# PCB_Maze.net
KiCad netlist of a schematic drawn in EAGLE
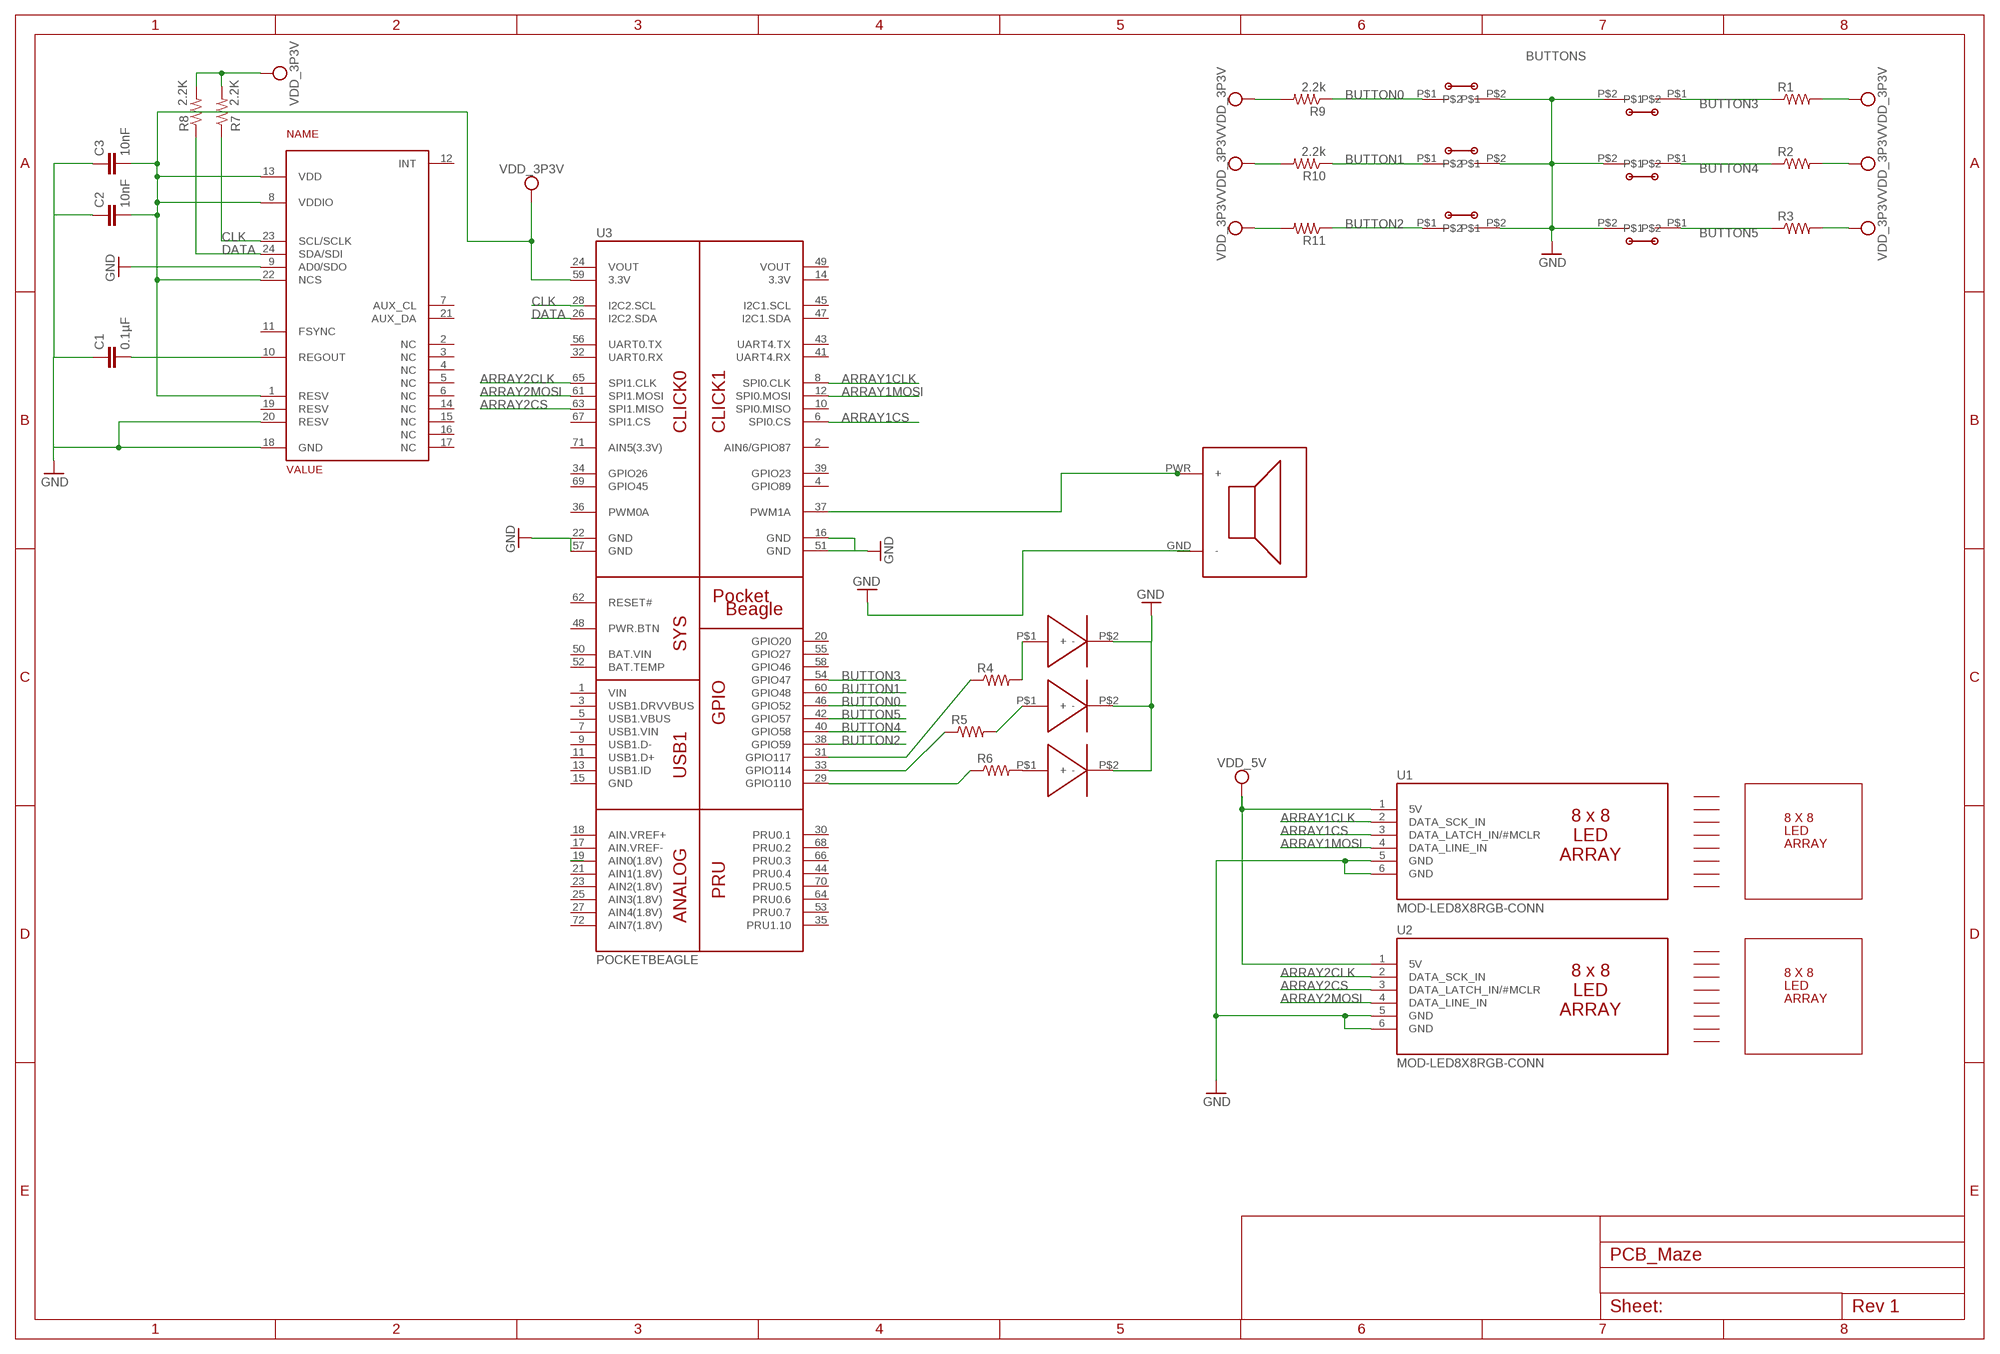
[diagram p0: schematic, sheet 1]

(export (version "E")
  (design (tool "Eeschema 10.0.6"))
  (components
    (comp (ref "C1")
      (value "0.1µF")
      (footprint "eagle-import:C0402")
      (libsource (lib "eagle-import") (part "C_C0402"))
    )
    (comp (ref "C2")
      (value "10nF")
      (footprint "eagle-import:C0402")
      (libsource (lib "eagle-import") (part "C_C0402"))
    )
    (comp (ref "C3")
      (value "10nF")
      (footprint "eagle-import:C0402")
      (libsource (lib "eagle-import") (part "C_C0402"))
    )
    (comp (ref "R1")
      (value "R_R0402")
      (footprint "eagle-import:R0402")
      (libsource (lib "eagle-import") (part "R_R0402"))
    )
    (comp (ref "R2")
      (value "R_R0402")
      (footprint "eagle-import:R0402")
      (libsource (lib "eagle-import") (part "R_R0402"))
    )
    (comp (ref "R3")
      (value "R_R0402")
      (footprint "eagle-import:R0402")
      (libsource (lib "eagle-import") (part "R_R0402"))
    )
    (comp (ref "R4")
      (value "R_R0402")
      (footprint "eagle-import:R0402")
      (libsource (lib "eagle-import") (part "R_R0402"))
    )
    (comp (ref "R5")
      (value "R_R0402")
      (footprint "eagle-import:R0402")
      (libsource (lib "eagle-import") (part "R_R0402"))
    )
    (comp (ref "R6")
      (value "R_R0402")
      (footprint "eagle-import:R0402")
      (libsource (lib "eagle-import") (part "R_R0402"))
    )
    (comp (ref "R7")
      (value "2.2K")
      (footprint "eagle-import:R0402")
      (libsource (lib "eagle-import") (part "R_R0402"))
    )
    (comp (ref "R8")
      (value "2.2K")
      (footprint "eagle-import:R0402")
      (libsource (lib "eagle-import") (part "R_R0402"))
    )
    (comp (ref "R9")
      (value "2.2k")
      (footprint "eagle-import:R0402")
      (libsource (lib "eagle-import") (part "R_R0402"))
    )
    (comp (ref "R10")
      (value "2.2k")
      (footprint "eagle-import:R0402")
      (libsource (lib "eagle-import") (part "R_R0402"))
    )
    (comp (ref "R11")
      (value "R_R0402")
      (footprint "eagle-import:R0402")
      (libsource (lib "eagle-import") (part "R_R0402"))
    )
    (comp (ref "U$1")
      (value "BUTTON")
      (footprint "eagle-import:SC203")
      (libsource (lib "eagle-import") (part "BUTTON"))
    )
    (comp (ref "U$2")
      (value "BUTTON")
      (footprint "eagle-import:SC203")
      (libsource (lib "eagle-import") (part "BUTTON"))
    )
    (comp (ref "U$3")
      (value "BUTTON")
      (footprint "eagle-import:SC203")
      (libsource (lib "eagle-import") (part "BUTTON"))
    )
    (comp (ref "U$5")
      (value "BUTTON")
      (footprint "eagle-import:SC203")
      (libsource (lib "eagle-import") (part "BUTTON"))
    )
    (comp (ref "U$6")
      (value "BUTTON")
      (footprint "eagle-import:SC203")
      (libsource (lib "eagle-import") (part "BUTTON"))
    )
    (comp (ref "U$8")
      (value "LED")
      (footprint "eagle-import:C191TBKT")
      (libsource (lib "eagle-import") (part "LED"))
    )
    (comp (ref "U$9")
      (value "LED")
      (footprint "eagle-import:C191TBKT")
      (libsource (lib "eagle-import") (part "LED"))
    )
    (comp (ref "U$10")
      (value "LED")
      (footprint "eagle-import:C191TBKT")
      (libsource (lib "eagle-import") (part "LED"))
    )
    (comp (ref "U$11")
      (value "BUZZER")
      (footprint "eagle-import:CEM-1203")
      (libsource (lib "eagle-import") (part "BUZZER"))
    )
    (comp (ref "U$12")
      (value "MPU9250")
      (footprint "eagle-import:QFN_3MMX3MM")
      (libsource (lib "eagle-import") (part "MPU9250"))
    )
    (comp (ref "U$13")
      (value "BUTTON")
      (footprint "eagle-import:SC203")
      (libsource (lib "eagle-import") (part "BUTTON"))
    )
    (comp (ref "U1")
      (value "MOD-LED8X8RGB-CONN")
      (footprint "eagle-import:FE06W")
      (libsource (lib "eagle-import") (part "MOD-LED8X8RGB-CONN"))
    )
    (comp (ref "U2")
      (value "MOD-LED8X8RGB-CONN")
      (footprint "eagle-import:FE06W")
      (libsource (lib "eagle-import") (part "MOD-LED8X8RGB-CONN"))
    )
    (comp (ref "U3")
      (value "POCKETBEAGLE")
      (footprint "eagle-import:POCKETBEAGLE")
      (libsource (lib "eagle-import") (part "POCKETBEAGLE"))
    )
  )
  (nets
    (net (code "1") (name "/ARRAY1CLK") (class "Default")
      (node (ref "U1") (pin "2") (pinfunction "DATA_SCK_IN_2") (pintype "bidirectional"))
      (node (ref "U3") (pin "8") (pinfunction "SPI0.CLK_8") (pintype "bidirectional"))
    )
    (net (code "2") (name "/ARRAY1CS") (class "Default")
      (node (ref "U1") (pin "3") (pinfunction "DATA_LATCH_IN/#MCLR_3") (pintype "bidirectional"))
      (node (ref "U3") (pin "6") (pinfunction "SPI0.CS_6") (pintype "bidirectional"))
    )
    (net (code "3") (name "/ARRAY1MOSI") (class "Default")
      (node (ref "U1") (pin "4") (pinfunction "DATA_LINE_IN_4") (pintype "bidirectional"))
      (node (ref "U3") (pin "12") (pinfunction "SPI0.MOSI_12") (pintype "bidirectional"))
    )
    (net (code "4") (name "/ARRAY2CLK") (class "Default")
      (node (ref "U2") (pin "2") (pinfunction "DATA_SCK_IN_2") (pintype "bidirectional"))
      (node (ref "U3") (pin "65") (pinfunction "SPI1.CLK_65") (pintype "bidirectional"))
    )
    (net (code "5") (name "/ARRAY2CS") (class "Default")
      (node (ref "U2") (pin "3") (pinfunction "DATA_LATCH_IN/#MCLR_3") (pintype "bidirectional"))
      (node (ref "U3") (pin "63") (pinfunction "SPI1.MISO_63") (pintype "bidirectional"))
    )
    (net (code "6") (name "/ARRAY2MOSI") (class "Default")
      (node (ref "U2") (pin "4") (pinfunction "DATA_LINE_IN_4") (pintype "bidirectional"))
      (node (ref "U3") (pin "61") (pinfunction "SPI1.MOSI_61") (pintype "bidirectional"))
    )
    (net (code "7") (name "/BUTTON0") (class "Default")
      (node (ref "R9") (pin "1") (pinfunction "1_1") (pintype "passive"))
      (node (ref "U$5") (pin "P$1") (pinfunction "P$1_P$1") (pintype "bidirectional"))
      (node (ref "U3") (pin "46") (pinfunction "GPIO52_46") (pintype "bidirectional"))
    )
    (net (code "8") (name "/BUTTON1") (class "Default")
      (node (ref "R10") (pin "1") (pinfunction "1_1") (pintype "passive"))
      (node (ref "U$6") (pin "P$1") (pinfunction "P$1_P$1") (pintype "bidirectional"))
      (node (ref "U3") (pin "60") (pinfunction "GPIO48_60") (pintype "bidirectional"))
    )
    (net (code "9") (name "/BUTTON2") (class "Default")
      (node (ref "R11") (pin "1") (pinfunction "1_1") (pintype "passive"))
      (node (ref "U$13") (pin "P$1") (pinfunction "P$1_P$1") (pintype "bidirectional"))
      (node (ref "U3") (pin "38") (pinfunction "GPIO59_38") (pintype "bidirectional"))
    )
    (net (code "10") (name "/BUTTON3") (class "Default")
      (node (ref "R1") (pin "1") (pinfunction "1_1") (pintype "passive"))
      (node (ref "U$1") (pin "P$1") (pinfunction "P$1_P$1") (pintype "bidirectional"))
      (node (ref "U3") (pin "54") (pinfunction "GPIO47_54") (pintype "bidirectional"))
    )
    (net (code "11") (name "/BUTTON4") (class "Default")
      (node (ref "R2") (pin "1") (pinfunction "1_1") (pintype "passive"))
      (node (ref "U$2") (pin "P$1") (pinfunction "P$1_P$1") (pintype "bidirectional"))
      (node (ref "U3") (pin "40") (pinfunction "GPIO58_40") (pintype "bidirectional"))
    )
    (net (code "12") (name "/BUTTON5") (class "Default")
      (node (ref "R3") (pin "1") (pinfunction "1_1") (pintype "passive"))
      (node (ref "U$3") (pin "P$1") (pinfunction "P$1_P$1") (pintype "bidirectional"))
      (node (ref "U3") (pin "42") (pinfunction "GPIO57_42") (pintype "bidirectional"))
    )
    (net (code "13") (name "/CLK") (class "Default")
      (node (ref "R7") (pin "1") (pinfunction "1_1") (pintype "passive"))
      (node (ref "U$12") (pin "23") (pinfunction "SCL/SCLK_23") (pintype "bidirectional"))
      (node (ref "U3") (pin "28") (pinfunction "I2C2.SCL_28") (pintype "bidirectional"))
    )
    (net (code "14") (name "/DATA") (class "Default")
      (node (ref "R8") (pin "1") (pinfunction "1_1") (pintype "passive"))
      (node (ref "U$12") (pin "24") (pinfunction "SDA/SDI_24") (pintype "bidirectional"))
      (node (ref "U3") (pin "26") (pinfunction "I2C2.SDA_26") (pintype "bidirectional"))
    )
    (net (code "15") (name "GND") (class "Default")
      (node (ref "C1") (pin "1") (pinfunction "1_1") (pintype "passive"))
      (node (ref "C2") (pin "1") (pinfunction "1_1") (pintype "passive"))
      (node (ref "C3") (pin "1") (pinfunction "1_1") (pintype "passive"))
      (node (ref "U$1") (pin "P$2") (pinfunction "P$2_P$2") (pintype "bidirectional"))
      (node (ref "U$10") (pin "P$2") (pinfunction "-_P$2") (pintype "bidirectional"))
      (node (ref "U$12") (pin "18") (pinfunction "GND_18") (pintype "bidirectional"))
      (node (ref "U$12") (pin "20") (pinfunction "RESV_20") (pintype "bidirectional"))
      (node (ref "U$12") (pin "9") (pinfunction "AD0/SDO_9") (pintype "bidirectional"))
      (node (ref "U$13") (pin "P$2") (pinfunction "P$2_P$2") (pintype "bidirectional"))
      (node (ref "U$2") (pin "P$2") (pinfunction "P$2_P$2") (pintype "bidirectional"))
      (node (ref "U$3") (pin "P$2") (pinfunction "P$2_P$2") (pintype "bidirectional"))
      (node (ref "U$5") (pin "P$2") (pinfunction "P$2_P$2") (pintype "bidirectional"))
      (node (ref "U$6") (pin "P$2") (pinfunction "P$2_P$2") (pintype "bidirectional"))
      (node (ref "U$8") (pin "P$2") (pinfunction "-_P$2") (pintype "bidirectional"))
      (node (ref "U$9") (pin "P$2") (pinfunction "-_P$2") (pintype "bidirectional"))
      (node (ref "U1") (pin "5") (pinfunction "GND_5") (pintype "bidirectional"))
      (node (ref "U1") (pin "6") (pinfunction "GND_6") (pintype "bidirectional"))
      (node (ref "U2") (pin "5") (pinfunction "GND_5") (pintype "bidirectional"))
      (node (ref "U2") (pin "6") (pinfunction "GND_6") (pintype "bidirectional"))
      (node (ref "U3") (pin "16") (pinfunction "GND_16") (pintype "bidirectional"))
      (node (ref "U3") (pin "22") (pinfunction "GND_22") (pintype "bidirectional"))
      (node (ref "U3") (pin "51") (pinfunction "GND_51") (pintype "bidirectional"))
      (node (ref "U3") (pin "57") (pinfunction "GND_57") (pintype "bidirectional"))
    )
    (net (code "16") (name "Net-(U$8-+)") (class "Default")
      (node (ref "R4") (pin "2") (pinfunction "2_2") (pintype "passive"))
      (node (ref "U$8") (pin "P$1") (pinfunction "+_P$1") (pintype "bidirectional"))
    )
    (net (code "17") (name "Net-(U$9-+)") (class "Default")
      (node (ref "R5") (pin "2") (pinfunction "2_2") (pintype "passive"))
      (node (ref "U$9") (pin "P$1") (pinfunction "+_P$1") (pintype "bidirectional"))
    )
    (net (code "18") (name "Net-(U$10-+)") (class "Default")
      (node (ref "R6") (pin "2") (pinfunction "2_2") (pintype "passive"))
      (node (ref "U$10") (pin "P$1") (pinfunction "+_P$1") (pintype "bidirectional"))
    )
    (net (code "19") (name "Net-(U$11-+)") (class "Default")
      (node (ref "U$11") (pin "PWR") (pinfunction "+_PWR") (pintype "bidirectional"))
      (node (ref "U3") (pin "37") (pinfunction "PWM1A_37") (pintype "bidirectional"))
    )
    (net (code "20") (name "Net-(U$12-REGOUT)") (class "Default")
      (node (ref "C1") (pin "2") (pinfunction "2_2") (pintype "passive"))
      (node (ref "U$12") (pin "10") (pinfunction "REGOUT_10") (pintype "bidirectional"))
    )
    (net (code "21") (name "Net-(U3-GPIO110)") (class "Default")
      (node (ref "R6") (pin "1") (pinfunction "1_1") (pintype "passive"))
      (node (ref "U3") (pin "29") (pinfunction "GPIO110_29") (pintype "bidirectional"))
    )
    (net (code "22") (name "Net-(U3-GPIO114)") (class "Default")
      (node (ref "R5") (pin "1") (pinfunction "1_1") (pintype "passive"))
      (node (ref "U3") (pin "33") (pinfunction "GPIO114_33") (pintype "bidirectional"))
    )
    (net (code "23") (name "Net-(U3-GPIO117)") (class "Default")
      (node (ref "R4") (pin "1") (pinfunction "1_1") (pintype "passive"))
      (node (ref "U3") (pin "31") (pinfunction "GPIO117_31") (pintype "bidirectional"))
    )
    (net (code "24") (name "VDD_3P3V") (class "Default")
      (node (ref "C2") (pin "2") (pinfunction "2_2") (pintype "passive"))
      (node (ref "C3") (pin "2") (pinfunction "2_2") (pintype "passive"))
      (node (ref "R1") (pin "2") (pinfunction "2_2") (pintype "passive"))
      (node (ref "R10") (pin "2") (pinfunction "2_2") (pintype "passive"))
      (node (ref "R11") (pin "2") (pinfunction "2_2") (pintype "passive"))
      (node (ref "R2") (pin "2") (pinfunction "2_2") (pintype "passive"))
      (node (ref "R3") (pin "2") (pinfunction "2_2") (pintype "passive"))
      (node (ref "R7") (pin "2") (pinfunction "2_2") (pintype "passive"))
      (node (ref "R8") (pin "2") (pinfunction "2_2") (pintype "passive"))
      (node (ref "R9") (pin "2") (pinfunction "2_2") (pintype "passive"))
      (node (ref "U$12") (pin "1") (pinfunction "RESV_1") (pintype "bidirectional"))
      (node (ref "U$12") (pin "13") (pinfunction "VDD_13") (pintype "bidirectional"))
      (node (ref "U$12") (pin "22") (pinfunction "NCS_22") (pintype "bidirectional"))
      (node (ref "U$12") (pin "8") (pinfunction "VDDIO_8") (pintype "bidirectional"))
      (node (ref "U3") (pin "59") (pinfunction "3.3V_59") (pintype "bidirectional"))
    )
    (net (code "25") (name "VDD_5V") (class "Default")
      (node (ref "U1") (pin "1") (pinfunction "5V_1") (pintype "bidirectional"))
      (node (ref "U2") (pin "1") (pinfunction "5V_1") (pintype "bidirectional"))
    )
    (net (code "26") (name "unconnected-(U$11---PadGND)") (class "Default")
      (node (ref "U$11") (pin "GND") (pinfunction "-_GND") (pintype "bidirectional"))
    )
    (net (code "27") (name "unconnected-(U$12-AUX_CL-Pad7)") (class "Default")
      (node (ref "U$12") (pin "7") (pinfunction "AUX_CL_7") (pintype "bidirectional"))
    )
    (net (code "28") (name "unconnected-(U$12-AUX_DA-Pad21)") (class "Default")
      (node (ref "U$12") (pin "21") (pinfunction "AUX_DA_21") (pintype "bidirectional"))
    )
    (net (code "29") (name "unconnected-(U$12-FSYNC-Pad11)") (class "Default")
      (node (ref "U$12") (pin "11") (pinfunction "FSYNC_11") (pintype "bidirectional"))
    )
    (net (code "30") (name "unconnected-(U$12-INT-Pad12)") (class "Default")
      (node (ref "U$12") (pin "12") (pinfunction "INT_12") (pintype "bidirectional"))
    )
    (net (code "31") (name "unconnected-(U$12-NC-Pad2)") (class "Default")
      (node (ref "U$12") (pin "2") (pinfunction "NC_2") (pintype "bidirectional"))
    )
    (net (code "32") (name "unconnected-(U$12-NC-Pad3)") (class "Default")
      (node (ref "U$12") (pin "3") (pinfunction "NC_3") (pintype "bidirectional"))
    )
    (net (code "33") (name "unconnected-(U$12-NC-Pad4)") (class "Default")
      (node (ref "U$12") (pin "4") (pinfunction "NC_4") (pintype "bidirectional"))
    )
    (net (code "34") (name "unconnected-(U$12-NC-Pad5)") (class "Default")
      (node (ref "U$12") (pin "5") (pinfunction "NC_5") (pintype "bidirectional"))
    )
    (net (code "35") (name "unconnected-(U$12-NC-Pad6)") (class "Default")
      (node (ref "U$12") (pin "6") (pinfunction "NC_6") (pintype "bidirectional"))
    )
    (net (code "36") (name "unconnected-(U$12-NC-Pad14)") (class "Default")
      (node (ref "U$12") (pin "14") (pinfunction "NC_14") (pintype "bidirectional"))
    )
    (net (code "37") (name "unconnected-(U$12-NC-Pad15)") (class "Default")
      (node (ref "U$12") (pin "15") (pinfunction "NC_15") (pintype "bidirectional"))
    )
    (net (code "38") (name "unconnected-(U$12-NC-Pad16)") (class "Default")
      (node (ref "U$12") (pin "16") (pinfunction "NC_16") (pintype "bidirectional"))
    )
    (net (code "39") (name "unconnected-(U$12-NC-Pad17)") (class "Default")
      (node (ref "U$12") (pin "17") (pinfunction "NC_17") (pintype "bidirectional"))
    )
    (net (code "40") (name "unconnected-(U$12-RESV-Pad19)") (class "Default")
      (node (ref "U$12") (pin "19") (pinfunction "RESV_19") (pintype "bidirectional"))
    )
    (net (code "41") (name "unconnected-(U3-3.3V-Pad14)") (class "Default")
      (node (ref "U3") (pin "14") (pinfunction "3.3V_14") (pintype "bidirectional"))
    )
    (net (code "42") (name "unconnected-(U3-AIN.VREF+-Pad18)") (class "Default")
      (node (ref "U3") (pin "18") (pinfunction "AIN.VREF+_18") (pintype "bidirectional"))
    )
    (net (code "43") (name "unconnected-(U3-AIN.VREF--Pad17)") (class "Default")
      (node (ref "U3") (pin "17") (pinfunction "AIN.VREF-_17") (pintype "bidirectional"))
    )
    (net (code "44") (name "unconnected-(U3-AIN0(1.8V)-Pad19)") (class "Default")
      (node (ref "U3") (pin "19") (pinfunction "AIN0(1.8V)_19") (pintype "bidirectional"))
    )
    (net (code "45") (name "unconnected-(U3-AIN1(1.8V)-Pad21)") (class "Default")
      (node (ref "U3") (pin "21") (pinfunction "AIN1(1.8V)_21") (pintype "bidirectional"))
    )
    (net (code "46") (name "unconnected-(U3-AIN2(1.8V)-Pad23)") (class "Default")
      (node (ref "U3") (pin "23") (pinfunction "AIN2(1.8V)_23") (pintype "bidirectional"))
    )
    (net (code "47") (name "unconnected-(U3-AIN3(1.8V)-Pad25)") (class "Default")
      (node (ref "U3") (pin "25") (pinfunction "AIN3(1.8V)_25") (pintype "bidirectional"))
    )
    (net (code "48") (name "unconnected-(U3-AIN4(1.8V)-Pad27)") (class "Default")
      (node (ref "U3") (pin "27") (pinfunction "AIN4(1.8V)_27") (pintype "bidirectional"))
    )
    (net (code "49") (name "unconnected-(U3-AIN5(3.3V)-Pad71)") (class "Default")
      (node (ref "U3") (pin "71") (pinfunction "AIN5(3.3V)_71") (pintype "bidirectional"))
    )
    (net (code "50") (name "unconnected-(U3-AIN6{slash}GPIO87-Pad2)") (class "Default")
      (node (ref "U3") (pin "2") (pinfunction "AIN6/GPIO87_2") (pintype "bidirectional"))
    )
    (net (code "51") (name "unconnected-(U3-AIN7(1.8V)-Pad72)") (class "Default")
      (node (ref "U3") (pin "72") (pinfunction "AIN7(1.8V)_72") (pintype "bidirectional"))
    )
    (net (code "52") (name "unconnected-(U3-BAT.TEMP-Pad52)") (class "Default")
      (node (ref "U3") (pin "52") (pinfunction "BAT.TEMP_52") (pintype "bidirectional"))
    )
    (net (code "53") (name "unconnected-(U3-BAT.VIN-Pad50)") (class "Default")
      (node (ref "U3") (pin "50") (pinfunction "BAT.VIN_50") (pintype "bidirectional"))
    )
    (net (code "54") (name "unconnected-(U3-GND-Pad15)") (class "Default")
      (node (ref "U3") (pin "15") (pinfunction "GND_15") (pintype "bidirectional"))
    )
    (net (code "55") (name "unconnected-(U3-GPIO20-Pad20)") (class "Default")
      (node (ref "U3") (pin "20") (pinfunction "GPIO20_20") (pintype "bidirectional"))
    )
    (net (code "56") (name "unconnected-(U3-GPIO23-Pad39)") (class "Default")
      (node (ref "U3") (pin "39") (pinfunction "GPIO23_39") (pintype "bidirectional"))
    )
    (net (code "57") (name "unconnected-(U3-GPIO26-Pad34)") (class "Default")
      (node (ref "U3") (pin "34") (pinfunction "GPIO26_34") (pintype "bidirectional"))
    )
    (net (code "58") (name "unconnected-(U3-GPIO27-Pad55)") (class "Default")
      (node (ref "U3") (pin "55") (pinfunction "GPIO27_55") (pintype "bidirectional"))
    )
    (net (code "59") (name "unconnected-(U3-GPIO45-Pad69)") (class "Default")
      (node (ref "U3") (pin "69") (pinfunction "GPIO45_69") (pintype "bidirectional"))
    )
    (net (code "60") (name "unconnected-(U3-GPIO46-Pad58)") (class "Default")
      (node (ref "U3") (pin "58") (pinfunction "GPIO46_58") (pintype "bidirectional"))
    )
    (net (code "61") (name "unconnected-(U3-GPIO89-Pad4)") (class "Default")
      (node (ref "U3") (pin "4") (pinfunction "GPIO89_4") (pintype "bidirectional"))
    )
    (net (code "62") (name "unconnected-(U3-I2C1.SCL-Pad45)") (class "Default")
      (node (ref "U3") (pin "45") (pinfunction "I2C1.SCL_45") (pintype "bidirectional"))
    )
    (net (code "63") (name "unconnected-(U3-I2C1.SDA-Pad47)") (class "Default")
      (node (ref "U3") (pin "47") (pinfunction "I2C1.SDA_47") (pintype "bidirectional"))
    )
    (net (code "64") (name "unconnected-(U3-PRU0.1-Pad30)") (class "Default")
      (node (ref "U3") (pin "30") (pinfunction "PRU0.1_30") (pintype "bidirectional"))
    )
    (net (code "65") (name "unconnected-(U3-PRU0.2-Pad68)") (class "Default")
      (node (ref "U3") (pin "68") (pinfunction "PRU0.2_68") (pintype "bidirectional"))
    )
    (net (code "66") (name "unconnected-(U3-PRU0.3-Pad66)") (class "Default")
      (node (ref "U3") (pin "66") (pinfunction "PRU0.3_66") (pintype "bidirectional"))
    )
    (net (code "67") (name "unconnected-(U3-PRU0.4-Pad44)") (class "Default")
      (node (ref "U3") (pin "44") (pinfunction "PRU0.4_44") (pintype "bidirectional"))
    )
    (net (code "68") (name "unconnected-(U3-PRU0.5-Pad70)") (class "Default")
      (node (ref "U3") (pin "70") (pinfunction "PRU0.5_70") (pintype "bidirectional"))
    )
    (net (code "69") (name "unconnected-(U3-PRU0.6-Pad64)") (class "Default")
      (node (ref "U3") (pin "64") (pinfunction "PRU0.6_64") (pintype "bidirectional"))
    )
    (net (code "70") (name "unconnected-(U3-PRU0.7-Pad53)") (class "Default")
      (node (ref "U3") (pin "53") (pinfunction "PRU0.7_53") (pintype "bidirectional"))
    )
    (net (code "71") (name "unconnected-(U3-PRU1.10-Pad35)") (class "Default")
      (node (ref "U3") (pin "35") (pinfunction "PRU1.10_35") (pintype "bidirectional"))
    )
    (net (code "72") (name "unconnected-(U3-PWM0A-Pad36)") (class "Default")
      (node (ref "U3") (pin "36") (pinfunction "PWM0A_36") (pintype "bidirectional"))
    )
    (net (code "73") (name "unconnected-(U3-PWR.BTN-Pad48)") (class "Default")
      (node (ref "U3") (pin "48") (pinfunction "PWR.BTN_48") (pintype "bidirectional"))
    )
    (net (code "74") (name "unconnected-(U3-RESET#-Pad62)") (class "Default")
      (node (ref "U3") (pin "62") (pinfunction "RESET#_62") (pintype "bidirectional"))
    )
    (net (code "75") (name "unconnected-(U3-SPI0.MISO-Pad10)") (class "Default")
      (node (ref "U3") (pin "10") (pinfunction "SPI0.MISO_10") (pintype "bidirectional"))
    )
    (net (code "76") (name "unconnected-(U3-SPI1.CS-Pad67)") (class "Default")
      (node (ref "U3") (pin "67") (pinfunction "SPI1.CS_67") (pintype "bidirectional"))
    )
    (net (code "77") (name "unconnected-(U3-UART0.RX-Pad32)") (class "Default")
      (node (ref "U3") (pin "32") (pinfunction "UART0.RX_32") (pintype "bidirectional"))
    )
    (net (code "78") (name "unconnected-(U3-UART0.TX-Pad56)") (class "Default")
      (node (ref "U3") (pin "56") (pinfunction "UART0.TX_56") (pintype "bidirectional"))
    )
    (net (code "79") (name "unconnected-(U3-UART4.RX-Pad41)") (class "Default")
      (node (ref "U3") (pin "41") (pinfunction "UART4.RX_41") (pintype "bidirectional"))
    )
    (net (code "80") (name "unconnected-(U3-UART4.TX-Pad43)") (class "Default")
      (node (ref "U3") (pin "43") (pinfunction "UART4.TX_43") (pintype "bidirectional"))
    )
    (net (code "81") (name "unconnected-(U3-USB1.D+-Pad11)") (class "Default")
      (node (ref "U3") (pin "11") (pinfunction "USB1.D+_11") (pintype "bidirectional"))
    )
    (net (code "82") (name "unconnected-(U3-USB1.D--Pad9)") (class "Default")
      (node (ref "U3") (pin "9") (pinfunction "USB1.D-_9") (pintype "bidirectional"))
    )
    (net (code "83") (name "unconnected-(U3-USB1.DRVVBUS-Pad3)") (class "Default")
      (node (ref "U3") (pin "3") (pinfunction "USB1.DRVVBUS_3") (pintype "bidirectional"))
    )
    (net (code "84") (name "unconnected-(U3-USB1.ID-Pad13)") (class "Default")
      (node (ref "U3") (pin "13") (pinfunction "USB1.ID_13") (pintype "bidirectional"))
    )
    (net (code "85") (name "unconnected-(U3-USB1.VBUS-Pad5)") (class "Default")
      (node (ref "U3") (pin "5") (pinfunction "USB1.VBUS_5") (pintype "bidirectional"))
    )
    (net (code "86") (name "unconnected-(U3-USB1.VIN-Pad7)") (class "Default")
      (node (ref "U3") (pin "7") (pinfunction "USB1.VIN_7") (pintype "bidirectional"))
    )
    (net (code "87") (name "unconnected-(U3-VIN-Pad1)") (class "Default")
      (node (ref "U3") (pin "1") (pinfunction "VIN_1") (pintype "bidirectional"))
    )
    (net (code "88") (name "unconnected-(U3-VOUT-Pad24)") (class "Default")
      (node (ref "U3") (pin "24") (pinfunction "VOUT_24") (pintype "bidirectional"))
    )
    (net (code "89") (name "unconnected-(U3-VOUT-Pad49)") (class "Default")
      (node (ref "U3") (pin "49") (pinfunction "VOUT_49") (pintype "bidirectional"))
    )
  )
)
